# Delibird_PIL.net
KiCad netlist of a schematic drawn in Altium Designer
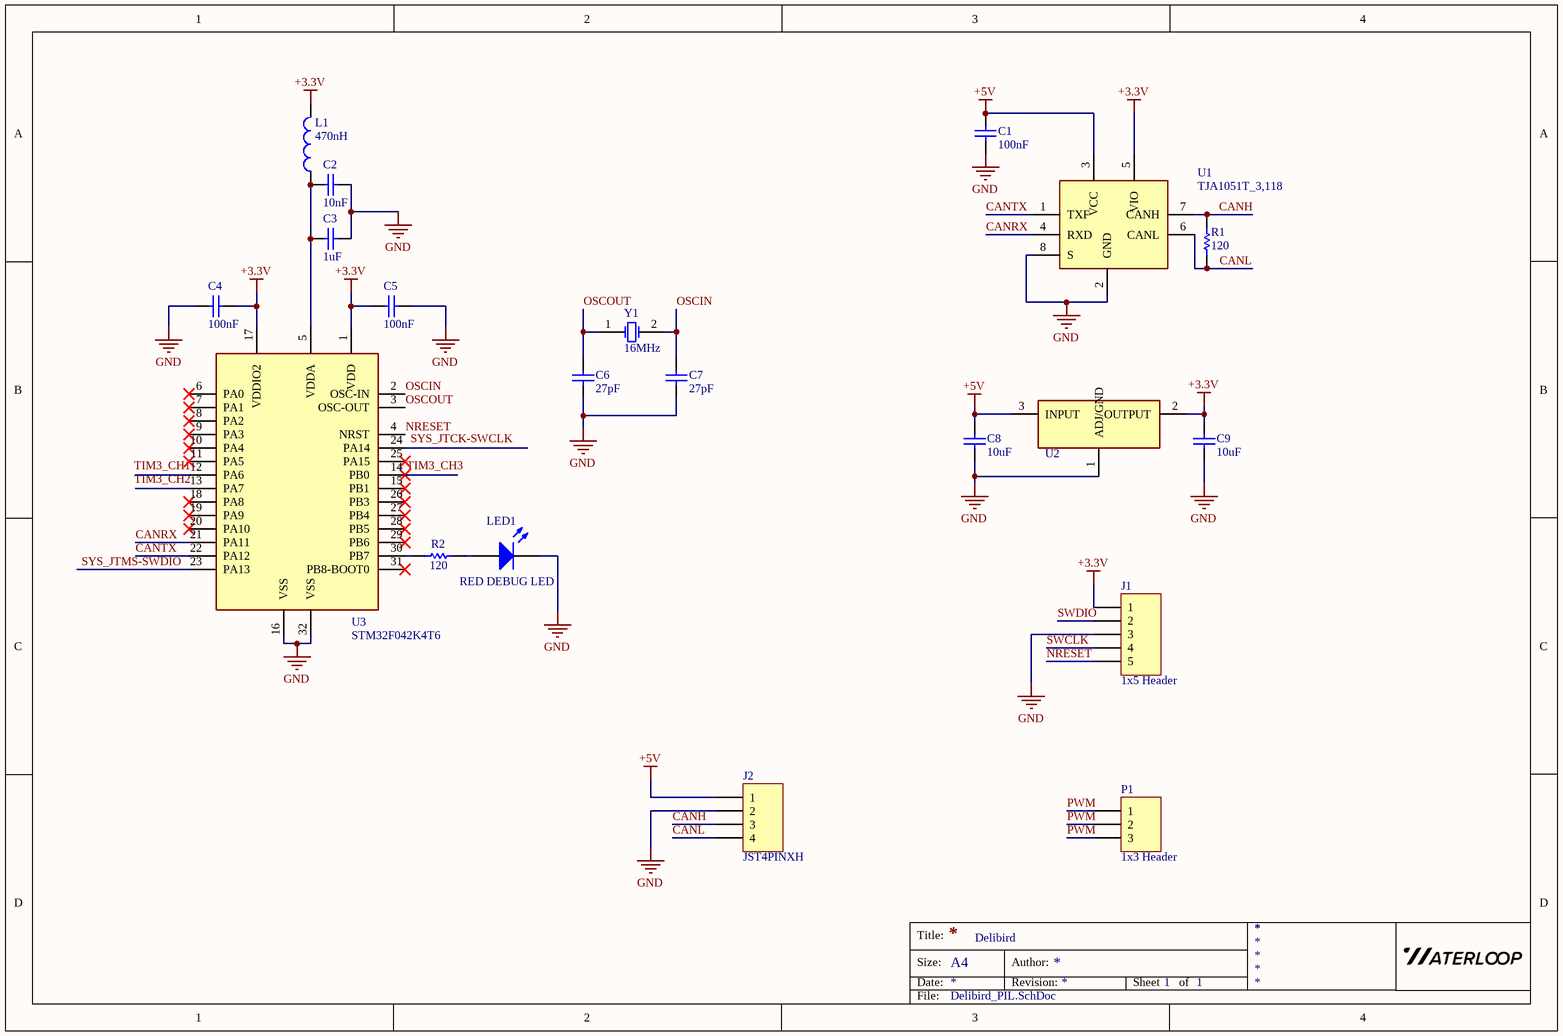
[diagram p0: Delibird_PIL.SchDoc]

(export (version "E")
  (design (tool "Eeschema 10.0.6"))
  (components
    (comp (ref "C1")
      (value "100nF")
      (footprint "0805 - Capacitor")
      (description "Nonpolarized Capacitor")
      (fields (field (name "Comment") "Capacitor - Nonpolarized"))
      (libsource (lib "General") (part "Capacitor - Nonpolarized"))
    )
    (comp (ref "C2")
      (value "10nF")
      (footprint "0805 - Capacitor")
      (description "Nonpolarized Capacitor")
      (fields (field (name "Comment") "Capacitor - Nonpolarized"))
      (libsource (lib "General") (part "Capacitor - Nonpolarized"))
    )
    (comp (ref "C3")
      (value "1uF")
      (footprint "0805 - Capacitor")
      (description "Nonpolarized Capacitor")
      (fields (field (name "Comment") "Capacitor - Nonpolarized"))
      (libsource (lib "General") (part "Capacitor - Nonpolarized"))
    )
    (comp (ref "C4")
      (value "100nF")
      (footprint "0805 - Capacitor")
      (description "Nonpolarized Capacitor")
      (fields (field (name "Comment") "Capacitor - Nonpolarized"))
      (libsource (lib "General") (part "Capacitor - Nonpolarized"))
    )
    (comp (ref "C5")
      (value "100nF")
      (footprint "0805 - Capacitor")
      (description "Nonpolarized Capacitor")
      (fields (field (name "Comment") "Capacitor - Nonpolarized"))
      (libsource (lib "General") (part "Capacitor - Nonpolarized"))
    )
    (comp (ref "C6")
      (value "27pF")
      (footprint "0805 - Capacitor")
      (description "Nonpolarized Capacitor")
      (fields (field (name "Comment") "Capacitor - Nonpolarized"))
      (libsource (lib "General") (part "Capacitor - Nonpolarized"))
    )
    (comp (ref "C7")
      (value "27pF")
      (footprint "0805 - Capacitor")
      (description "Nonpolarized Capacitor")
      (fields (field (name "Comment") "Capacitor - Nonpolarized"))
      (libsource (lib "General") (part "Capacitor - Nonpolarized"))
    )
    (comp (ref "C8")
      (value "10uF")
      (footprint "0805 - Capacitor")
      (description "Nonpolarized Capacitor")
      (fields (field (name "Comment") "Capacitor - Nonpolarized"))
      (libsource (lib "General") (part "Capacitor - Nonpolarized"))
    )
    (comp (ref "C9")
      (value "10uF")
      (footprint "0805 - Capacitor")
      (description "Nonpolarized Capacitor")
      (fields (field (name "Comment") "Capacitor - Nonpolarized"))
      (libsource (lib "General") (part "Capacitor - Nonpolarized"))
    )
    (comp (ref "J1")
      (value "1x5 Header")
      (footprint "HDR1X5")
      (description "1x5 Pin Header")
      (libsource (lib "GeneralConnectors") (part "1x5 Header"))
    )
    (comp (ref "J2")
      (value "JST4PINXH")
      (footprint "B4B-XH")
      (description "1x4 Pin Header")
      (libsource (lib "GeneralConnectors") (part "1x4 Header"))
    )
    (comp (ref "L1")
      (value "470nH")
      (footprint "0805 - Capacitor")
      (description "Inductor")
      (libsource (lib "General") (part "Inductor"))
    )
    (comp (ref "LED1")
      (value "RED DEBUG LED")
      (footprint "0805 - Resistor")
      (description "Light Emitting Diode")
      (libsource (lib "General") (part "LED"))
    )
    (comp (ref "P1")
      (value "1x3 Header")
      (footprint "HDR1X3")
      (description "1x3 Pin Header")
      (libsource (lib "GeneralConnectors") (part "1x3 Header"))
    )
    (comp (ref "R1")
      (value "120")
      (footprint "0603 - Resistor")
      (description "Resistor")
      (libsource (lib "General") (part "Resistor"))
    )
    (comp (ref "R2")
      (value "120")
      (footprint "0603 - Resistor")
      (description "Resistor")
      (libsource (lib "General") (part "Resistor"))
    )
    (comp (ref "U1")
      (value "TJA1051T_3,118")
      (footprint "TJA1051T/3,118")
      (description "CAN Transceiver IC 4.5V-5.5V 250ns")
      (fields (field (name "MANUFACTURER") "NXP") (field (name "MANUFACTURER PART NUMBER") "TJA1051T/3,118"))
      (libsource (lib "GeneralComponents") (part "TJA1051T_3,118"))
    )
    (comp (ref "U2")
      (value "TLV1117-33IDCYR")
      (footprint "TLV1117")
      (description "Linear Voltage Regulator IC 3.3V 800MA SOT223-4")
      (fields (field (name "MANUFACTURER") "Texas Instruments"))
      (libsource (lib "GeneralComponents") (part "TLV1117-33IDCYR"))
    )
    (comp (ref "U3")
      (value "STM32F042K4T6")
      (footprint "QFP80P900X900X160-32N")
      (description "Microcontroller")
      (fields (field (name "MOUSER PART NUMBER") "511-STM32F042K4T6"))
      (libsource (lib "Embedded") (part "STM32F042K4T6"))
    )
    (comp (ref "Y1")
      (value "16MHz")
      (footprint "2-SMD NO LEAD CRSYSTAL")
      (description "Crystal Oscillator")
      (fields (field (name "Comment") "Oscillator"))
      (libsource (lib "General") (part "Oscillator"))
    )
  )
  (nets
    (net (code "1") (name "+3.3V") (class "Default")
      (node (ref "C4") (pin "1") (pinfunction "1_1") (pintype "passive"))
      (node (ref "C5") (pin "2") (pinfunction "2_2") (pintype "passive"))
      (node (ref "C9") (pin "2") (pinfunction "2_2") (pintype "passive"))
      (node (ref "J1") (pin "1") (pinfunction "1_1") (pintype "passive"))
      (node (ref "L1") (pin "2") (pinfunction "2_2") (pintype "passive"))
      (node (ref "U1") (pin "5") (pinfunction "VIO_5") (pintype "passive"))
      (node (ref "U2") (pin "2") (pinfunction "OUTPUT_2") (pintype "passive"))
      (node (ref "U3") (pin "1") (pinfunction "VDD_1") (pintype "passive"))
      (node (ref "U3") (pin "17") (pinfunction "VDDIO2_17") (pintype "passive"))
    )
    (net (code "2") (name "+5V") (class "Default")
      (node (ref "C1") (pin "2") (pinfunction "2_2") (pintype "passive"))
      (node (ref "C8") (pin "1") (pinfunction "1_1") (pintype "passive"))
      (node (ref "J2") (pin "1") (pinfunction "1_1") (pintype "passive"))
      (node (ref "U1") (pin "3") (pinfunction "VCC_3") (pintype "passive"))
      (node (ref "U2") (pin "3") (pinfunction "INPUT_3") (pintype "passive"))
    )
    (net (code "3") (name "/CANH") (class "Default")
      (node (ref "J2") (pin "3") (pinfunction "3_3") (pintype "passive"))
      (node (ref "R1") (pin "2") (pinfunction "2_2") (pintype "passive"))
      (node (ref "U1") (pin "7") (pinfunction "CANH_7") (pintype "passive"))
    )
    (net (code "4") (name "/CANL") (class "Default")
      (node (ref "J2") (pin "4") (pinfunction "4_4") (pintype "passive"))
      (node (ref "R1") (pin "1") (pinfunction "1_1") (pintype "passive"))
      (node (ref "U1") (pin "6") (pinfunction "CANL_6") (pintype "passive"))
    )
    (net (code "5") (name "/CANRX") (class "Default")
      (node (ref "U1") (pin "4") (pinfunction "RXD_4") (pintype "passive"))
      (node (ref "U3") (pin "21") (pinfunction "PA11_21") (pintype "passive"))
    )
    (net (code "6") (name "/CANTX") (class "Default")
      (node (ref "U1") (pin "1") (pinfunction "TXF_1") (pintype "passive"))
      (node (ref "U3") (pin "22") (pinfunction "PA12_22") (pintype "passive"))
    )
    (net (code "7") (name "/NRESET") (class "Default")
      (node (ref "J1") (pin "5") (pinfunction "5_5") (pintype "passive"))
      (node (ref "U3") (pin "4") (pinfunction "NRST_4") (pintype "passive"))
    )
    (net (code "8") (name "/OSCIN") (class "Default")
      (node (ref "C7") (pin "2") (pinfunction "2_2") (pintype "passive"))
      (node (ref "U3") (pin "2") (pinfunction "OSC-IN_2") (pintype "passive"))
      (node (ref "Y1") (pin "2") (pinfunction "OSC2_2") (pintype "passive"))
    )
    (net (code "9") (name "/OSCOUT") (class "Default")
      (node (ref "C6") (pin "2") (pinfunction "2_2") (pintype "passive"))
      (node (ref "U3") (pin "3") (pinfunction "OSC-OUT_3") (pintype "passive"))
      (node (ref "Y1") (pin "1") (pinfunction "OSC1_1") (pintype "passive"))
    )
    (net (code "10") (name "/PWM") (class "Default")
      (node (ref "P1") (pin "1") (pinfunction "1_1") (pintype "passive"))
      (node (ref "P1") (pin "2") (pinfunction "2_2") (pintype "passive"))
      (node (ref "P1") (pin "3") (pinfunction "3_3") (pintype "passive"))
    )
    (net (code "11") (name "/SWCLK") (class "Default")
      (node (ref "J1") (pin "4") (pinfunction "4_4") (pintype "passive"))
    )
    (net (code "12") (name "/SWDIO") (class "Default")
      (node (ref "J1") (pin "2") (pinfunction "2_2") (pintype "passive"))
    )
    (net (code "14") (name "/SYS_JTMS-SWDIO") (class "Default")
      (node (ref "U3") (pin "23") (pinfunction "PA13_23") (pintype "passive"))
    )
    (net (code "18") (name "GND") (class "Default")
      (node (ref "C1") (pin "1") (pinfunction "1_1") (pintype "passive"))
      (node (ref "C2") (pin "2") (pinfunction "2_2") (pintype "passive"))
      (node (ref "C3") (pin "2") (pinfunction "2_2") (pintype "passive"))
      (node (ref "C4") (pin "2") (pinfunction "2_2") (pintype "passive"))
      (node (ref "C5") (pin "1") (pinfunction "1_1") (pintype "passive"))
      (node (ref "C6") (pin "1") (pinfunction "1_1") (pintype "passive"))
      (node (ref "C7") (pin "1") (pinfunction "1_1") (pintype "passive"))
      (node (ref "C8") (pin "2") (pinfunction "2_2") (pintype "passive"))
      (node (ref "C9") (pin "1") (pinfunction "1_1") (pintype "passive"))
      (node (ref "J1") (pin "3") (pinfunction "3_3") (pintype "passive"))
      (node (ref "J2") (pin "2") (pinfunction "2_2") (pintype "passive"))
      (node (ref "LED1") (pin "2") (pinfunction "K_2") (pintype "passive"))
      (node (ref "U1") (pin "2") (pinfunction "GND_2") (pintype "passive"))
      (node (ref "U1") (pin "8") (pinfunction "S_8") (pintype "passive"))
      (node (ref "U2") (pin "1") (pinfunction "ADJ/GND_1") (pintype "passive"))
      (node (ref "U3") (pin "16") (pinfunction "VSS_16") (pintype "passive"))
      (node (ref "U3") (pin "32") (pinfunction "VSS_32") (pintype "passive"))
    )
    (net (code "19") (name "Net-(LED1-A)") (class "Default")
      (node (ref "LED1") (pin "1") (pinfunction "A_1") (pintype "passive"))
      (node (ref "R2") (pin "2") (pinfunction "2_2") (pintype "passive"))
    )
    (net (code "20") (name "Net-(U3-PB7)") (class "Default")
      (node (ref "R2") (pin "1") (pinfunction "1_1") (pintype "passive"))
      (node (ref "U3") (pin "30") (pinfunction "PB7_30") (pintype "passive"))
    )
    (net (code "21") (name "Net-(U3-VDDA)") (class "Default")
      (node (ref "C2") (pin "1") (pinfunction "1_1") (pintype "passive"))
      (node (ref "C3") (pin "1") (pinfunction "1_1") (pintype "passive"))
      (node (ref "L1") (pin "1") (pinfunction "1_1") (pintype "passive"))
      (node (ref "U3") (pin "5") (pinfunction "VDDA_5") (pintype "passive"))
    )
    (net (code "22") (name "unconnected-(U3-PA0-Pad6)") (class "Default")
      (node (ref "U3") (pin "6") (pinfunction "PA0_6") (pintype "passive+no_connect"))
    )
    (net (code "23") (name "unconnected-(U3-PA1-Pad7)") (class "Default")
      (node (ref "U3") (pin "7") (pinfunction "PA1_7") (pintype "passive+no_connect"))
    )
    (net (code "24") (name "unconnected-(U3-PA2-Pad8)") (class "Default")
      (node (ref "U3") (pin "8") (pinfunction "PA2_8") (pintype "passive+no_connect"))
    )
    (net (code "25") (name "unconnected-(U3-PA3-Pad9)") (class "Default")
      (node (ref "U3") (pin "9") (pinfunction "PA3_9") (pintype "passive+no_connect"))
    )
    (net (code "26") (name "unconnected-(U3-PA4-Pad10)") (class "Default")
      (node (ref "U3") (pin "10") (pinfunction "PA4_10") (pintype "passive+no_connect"))
    )
    (net (code "27") (name "unconnected-(U3-PA5-Pad11)") (class "Default")
      (node (ref "U3") (pin "11") (pinfunction "PA5_11") (pintype "passive+no_connect"))
    )
    (net (code "28") (name "unconnected-(U3-PA6-Pad12)") (class "Default")
      (node (ref "U3") (pin "12") (pinfunction "PA6_12") (pintype "passive"))
    )
    (net (code "29") (name "unconnected-(U3-PA7-Pad13)") (class "Default")
      (node (ref "U3") (pin "13") (pinfunction "PA7_13") (pintype "passive"))
    )
    (net (code "30") (name "unconnected-(U3-PA8-Pad18)") (class "Default")
      (node (ref "U3") (pin "18") (pinfunction "PA8_18") (pintype "passive+no_connect"))
    )
    (net (code "31") (name "unconnected-(U3-PA9-Pad19)") (class "Default")
      (node (ref "U3") (pin "19") (pinfunction "PA9_19") (pintype "passive+no_connect"))
    )
    (net (code "32") (name "unconnected-(U3-PA10-Pad20)") (class "Default")
      (node (ref "U3") (pin "20") (pinfunction "PA10_20") (pintype "passive+no_connect"))
    )
    (net (code "33") (name "unconnected-(U3-PA14-Pad24)") (class "Default")
      (node (ref "U3") (pin "24") (pinfunction "PA14_24") (pintype "passive"))
    )
    (net (code "34") (name "unconnected-(U3-PA15-Pad25)") (class "Default")
      (node (ref "U3") (pin "25") (pinfunction "PA15_25") (pintype "passive+no_connect"))
    )
    (net (code "35") (name "unconnected-(U3-PB0-Pad14)") (class "Default")
      (node (ref "U3") (pin "14") (pinfunction "PB0_14") (pintype "passive+no_connect"))
    )
    (net (code "36") (name "unconnected-(U3-PB1-Pad15)") (class "Default")
      (node (ref "U3") (pin "15") (pinfunction "PB1_15") (pintype "passive+no_connect"))
    )
    (net (code "37") (name "unconnected-(U3-PB3-Pad26)") (class "Default")
      (node (ref "U3") (pin "26") (pinfunction "PB3_26") (pintype "passive+no_connect"))
    )
    (net (code "38") (name "unconnected-(U3-PB4-Pad27)") (class "Default")
      (node (ref "U3") (pin "27") (pinfunction "PB4_27") (pintype "passive+no_connect"))
    )
    (net (code "39") (name "unconnected-(U3-PB5-Pad28)") (class "Default")
      (node (ref "U3") (pin "28") (pinfunction "PB5_28") (pintype "passive+no_connect"))
    )
    (net (code "40") (name "unconnected-(U3-PB6-Pad29)") (class "Default")
      (node (ref "U3") (pin "29") (pinfunction "PB6_29") (pintype "passive+no_connect"))
    )
    (net (code "41") (name "unconnected-(U3-PB8-BOOT0-Pad31)") (class "Default")
      (node (ref "U3") (pin "31") (pinfunction "PB8-BOOT0_31") (pintype "passive+no_connect"))
    )
  )
)
